# new_moisture_ckt_design_using_ESP32.net
KiCad netlist of a schematic drawn in EAGLE
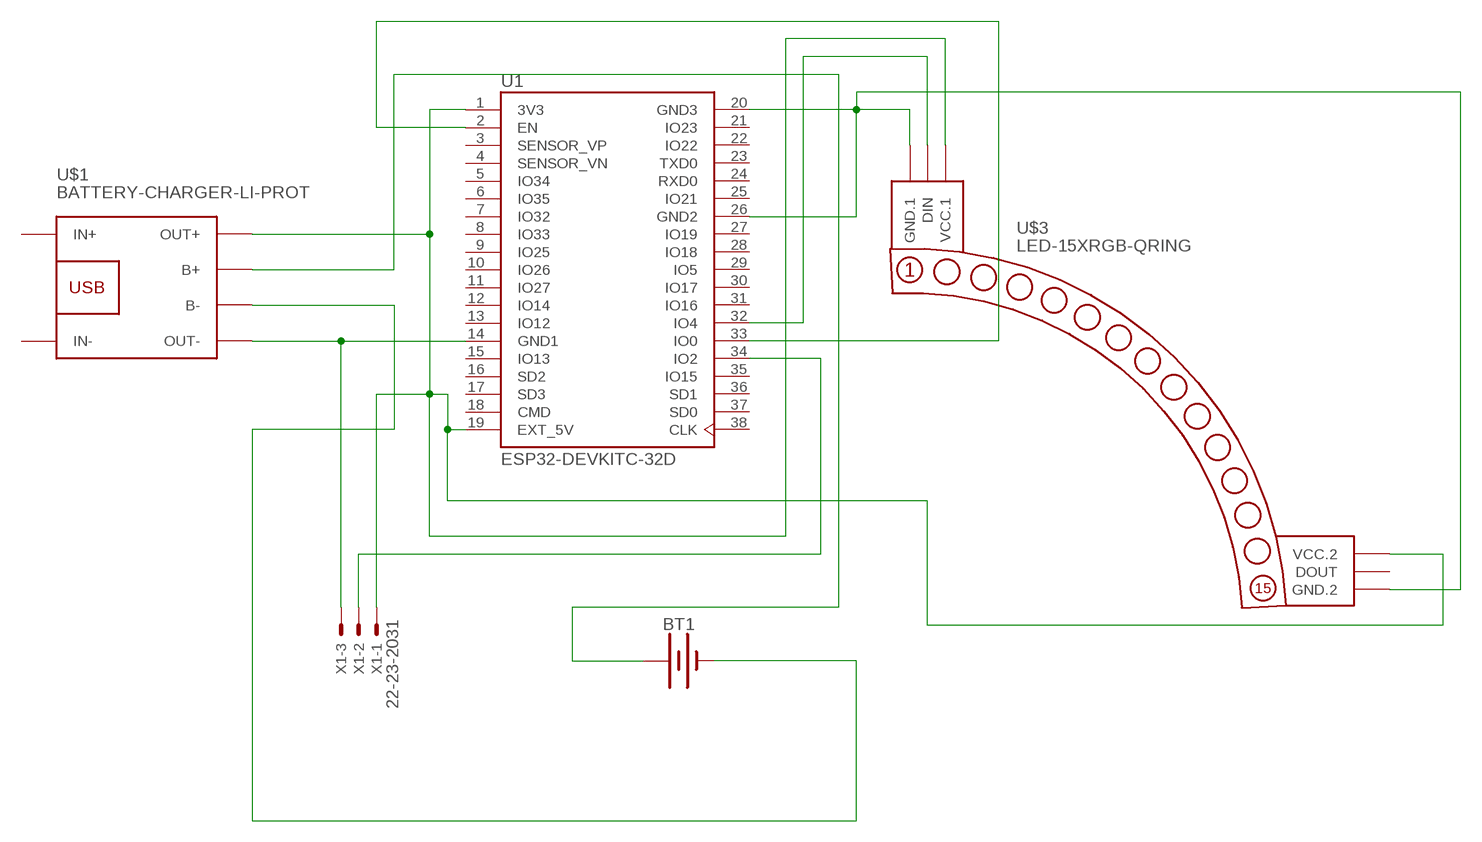
[diagram p0: schematic, sheet 1]

(export (version "E")
  (design (tool "Eeschema 10.0.6"))
  (components
    (comp (ref "BT1")
      (value "BATTERY-12MM_PTH")
      (footprint "eagle-import:BATTCON_12MM_PTH")
      (libsource (lib "eagle-import") (part "BATTERY-12MM_PTH"))
    )
    (comp (ref "U$1")
      (value "BATTERY-CHARGER-LI-PROT")
      (footprint "eagle-import:BATTERY-CHARGER-LI-PROT")
      (libsource (lib "eagle-import") (part "BATTERY-CHARGER-LI-PROT"))
    )
    (comp (ref "U$3")
      (value "LED-15XRGB-QRING")
      (footprint "eagle-import:LED-15XRGB-QRING")
      (libsource (lib "eagle-import") (part "LED-15XRGB-QRING"))
    )
    (comp (ref "U1")
      (value "ESP32-DEVKITC-32D")
      (footprint "eagle-import:MODULE_ESP32-DEVKITC-32D")
      (fields (field (name "MF") "Espressif Systems"))
      (libsource (lib "eagle-import") (part "ESP32-DEVKITC-32D"))
    )
    (comp (ref "X1")
      (value "22-23-2031")
      (footprint "eagle-import:22-23-2031")
      (fields (field (name "MF") "MOLEX"))
      (libsource (lib "eagle-import") (part "22-23-2031"))
    )
  )
  (nets
    (net (code "1") (name "Net-(BT1-+)") (class "Default")
      (node (ref "BT1") (pin "VCC@1") (pinfunction "+_VCC@1") (pintype "power_in"))
      (node (ref "U$1") (pin "B+") (pinfunction "B+_B+") (pintype "bidirectional"))
    )
    (net (code "2") (name "Net-(BT1--)") (class "Default")
      (node (ref "BT1") (pin "GND") (pinfunction "-_GND") (pintype "power_in"))
      (node (ref "U$1") (pin "B-") (pinfunction "B-_B-") (pintype "bidirectional"))
      (node (ref "U$1") (pin "OUT+") (pinfunction "OUT+_OUT+") (pintype "bidirectional"))
      (node (ref "U$3") (pin "3") (pinfunction "VCC.1_3") (pintype "power_in"))
      (node (ref "U$3") (pin "6") (pinfunction "VCC.2_6") (pintype "power_in"))
      (node (ref "U1") (pin "1") (pinfunction "3V3_1") (pintype "power_in"))
      (node (ref "U1") (pin "19") (pinfunction "EXT_5V_19") (pintype "power_in"))
      (node (ref "X1") (pin "1") (pinfunction "S_1") (pintype "passive"))
    )
    (net (code "3") (name "Net-(U$3-DIN)") (class "Default")
      (node (ref "U$3") (pin "2") (pinfunction "DIN_2") (pintype "input"))
      (node (ref "U1") (pin "32") (pinfunction "IO4_32") (pintype "bidirectional"))
    )
    (net (code "4") (name "Net-(U$3-GND.1)") (class "Default")
      (node (ref "U$3") (pin "1") (pinfunction "GND.1_1") (pintype "power_in"))
      (node (ref "U$3") (pin "4") (pinfunction "GND.2_4") (pintype "power_in"))
      (node (ref "U1") (pin "20") (pinfunction "GND3_20") (pintype "power_in"))
      (node (ref "U1") (pin "26") (pinfunction "GND2_26") (pintype "power_in"))
    )
    (net (code "5") (name "Net-(U1-EN)") (class "Default")
      (node (ref "U1") (pin "2") (pinfunction "EN_2") (pintype "input"))
      (node (ref "U1") (pin "33") (pinfunction "IO0_33") (pintype "bidirectional"))
    )
    (net (code "6") (name "Net-(U1-GND1)") (class "Default")
      (node (ref "U$1") (pin "OUT-") (pinfunction "OUT-_OUT-") (pintype "bidirectional"))
      (node (ref "U1") (pin "14") (pinfunction "GND1_14") (pintype "power_in"))
      (node (ref "X1") (pin "3") (pinfunction "S_3") (pintype "passive"))
    )
    (net (code "7") (name "Net-(U1-IO2)") (class "Default")
      (node (ref "U1") (pin "34") (pinfunction "IO2_34") (pintype "bidirectional"))
      (node (ref "X1") (pin "2") (pinfunction "S_2") (pintype "passive"))
    )
    (net (code "8") (name "unconnected-(U$1-PadIN+)") (class "Default")
      (node (ref "U$1") (pin "IN+") (pinfunction "IN+_IN+") (pintype "bidirectional"))
    )
    (net (code "9") (name "unconnected-(U$1-PadIN-)") (class "Default")
      (node (ref "U$1") (pin "IN-") (pinfunction "IN-_IN-") (pintype "bidirectional"))
    )
    (net (code "10") (name "unconnected-(U$3-DOUT-Pad5)") (class "Default")
      (node (ref "U$3") (pin "5") (pinfunction "DOUT_5") (pintype "output"))
    )
    (net (code "11") (name "unconnected-(U1-CLK-Pad38)") (class "Default")
      (node (ref "U1") (pin "38") (pinfunction "CLK_38") (pintype "input"))
    )
    (net (code "12") (name "unconnected-(U1-CMD-Pad18)") (class "Default")
      (node (ref "U1") (pin "18") (pinfunction "CMD_18") (pintype "bidirectional"))
    )
    (net (code "13") (name "unconnected-(U1-IO5-Pad29)") (class "Default")
      (node (ref "U1") (pin "29") (pinfunction "IO5_29") (pintype "bidirectional"))
    )
    (net (code "14") (name "unconnected-(U1-IO12-Pad13)") (class "Default")
      (node (ref "U1") (pin "13") (pinfunction "IO12_13") (pintype "bidirectional"))
    )
    (net (code "15") (name "unconnected-(U1-IO13-Pad15)") (class "Default")
      (node (ref "U1") (pin "15") (pinfunction "IO13_15") (pintype "bidirectional"))
    )
    (net (code "16") (name "unconnected-(U1-IO14-Pad12)") (class "Default")
      (node (ref "U1") (pin "12") (pinfunction "IO14_12") (pintype "bidirectional"))
    )
    (net (code "17") (name "unconnected-(U1-IO15-Pad35)") (class "Default")
      (node (ref "U1") (pin "35") (pinfunction "IO15_35") (pintype "bidirectional"))
    )
    (net (code "18") (name "unconnected-(U1-IO16-Pad31)") (class "Default")
      (node (ref "U1") (pin "31") (pinfunction "IO16_31") (pintype "bidirectional"))
    )
    (net (code "19") (name "unconnected-(U1-IO17-Pad30)") (class "Default")
      (node (ref "U1") (pin "30") (pinfunction "IO17_30") (pintype "bidirectional"))
    )
    (net (code "20") (name "unconnected-(U1-IO18-Pad28)") (class "Default")
      (node (ref "U1") (pin "28") (pinfunction "IO18_28") (pintype "bidirectional"))
    )
    (net (code "21") (name "unconnected-(U1-IO19-Pad27)") (class "Default")
      (node (ref "U1") (pin "27") (pinfunction "IO19_27") (pintype "bidirectional"))
    )
    (net (code "22") (name "unconnected-(U1-IO21-Pad25)") (class "Default")
      (node (ref "U1") (pin "25") (pinfunction "IO21_25") (pintype "bidirectional"))
    )
    (net (code "23") (name "unconnected-(U1-IO22-Pad22)") (class "Default")
      (node (ref "U1") (pin "22") (pinfunction "IO22_22") (pintype "bidirectional"))
    )
    (net (code "24") (name "unconnected-(U1-IO23-Pad21)") (class "Default")
      (node (ref "U1") (pin "21") (pinfunction "IO23_21") (pintype "bidirectional"))
    )
    (net (code "25") (name "unconnected-(U1-IO25-Pad9)") (class "Default")
      (node (ref "U1") (pin "9") (pinfunction "IO25_9") (pintype "bidirectional"))
    )
    (net (code "26") (name "unconnected-(U1-IO26-Pad10)") (class "Default")
      (node (ref "U1") (pin "10") (pinfunction "IO26_10") (pintype "bidirectional"))
    )
    (net (code "27") (name "unconnected-(U1-IO27-Pad11)") (class "Default")
      (node (ref "U1") (pin "11") (pinfunction "IO27_11") (pintype "bidirectional"))
    )
    (net (code "28") (name "unconnected-(U1-IO32-Pad7)") (class "Default")
      (node (ref "U1") (pin "7") (pinfunction "IO32_7") (pintype "bidirectional"))
    )
    (net (code "29") (name "unconnected-(U1-IO33-Pad8)") (class "Default")
      (node (ref "U1") (pin "8") (pinfunction "IO33_8") (pintype "bidirectional"))
    )
    (net (code "30") (name "unconnected-(U1-IO34-Pad5)") (class "Default")
      (node (ref "U1") (pin "5") (pinfunction "IO34_5") (pintype "bidirectional"))
    )
    (net (code "31") (name "unconnected-(U1-IO35-Pad6)") (class "Default")
      (node (ref "U1") (pin "6") (pinfunction "IO35_6") (pintype "bidirectional"))
    )
    (net (code "32") (name "unconnected-(U1-RXD0-Pad24)") (class "Default")
      (node (ref "U1") (pin "24") (pinfunction "RXD0_24") (pintype "input"))
    )
    (net (code "33") (name "unconnected-(U1-SD0-Pad37)") (class "Default")
      (node (ref "U1") (pin "37") (pinfunction "SD0_37") (pintype "bidirectional"))
    )
    (net (code "34") (name "unconnected-(U1-SD1-Pad36)") (class "Default")
      (node (ref "U1") (pin "36") (pinfunction "SD1_36") (pintype "bidirectional"))
    )
    (net (code "35") (name "unconnected-(U1-SD2-Pad16)") (class "Default")
      (node (ref "U1") (pin "16") (pinfunction "SD2_16") (pintype "bidirectional"))
    )
    (net (code "36") (name "unconnected-(U1-SD3-Pad17)") (class "Default")
      (node (ref "U1") (pin "17") (pinfunction "SD3_17") (pintype "bidirectional"))
    )
    (net (code "37") (name "unconnected-(U1-SENSOR_VN-Pad4)") (class "Default")
      (node (ref "U1") (pin "4") (pinfunction "SENSOR_VN_4") (pintype "input"))
    )
    (net (code "38") (name "unconnected-(U1-SENSOR_VP-Pad3)") (class "Default")
      (node (ref "U1") (pin "3") (pinfunction "SENSOR_VP_3") (pintype "input"))
    )
    (net (code "39") (name "unconnected-(U1-TXD0-Pad23)") (class "Default")
      (node (ref "U1") (pin "23") (pinfunction "TXD0_23") (pintype "output"))
    )
  )
)
